# DipSeq_panel_12HP_20150408.net
KiCad netlist of a schematic drawn in EAGLE
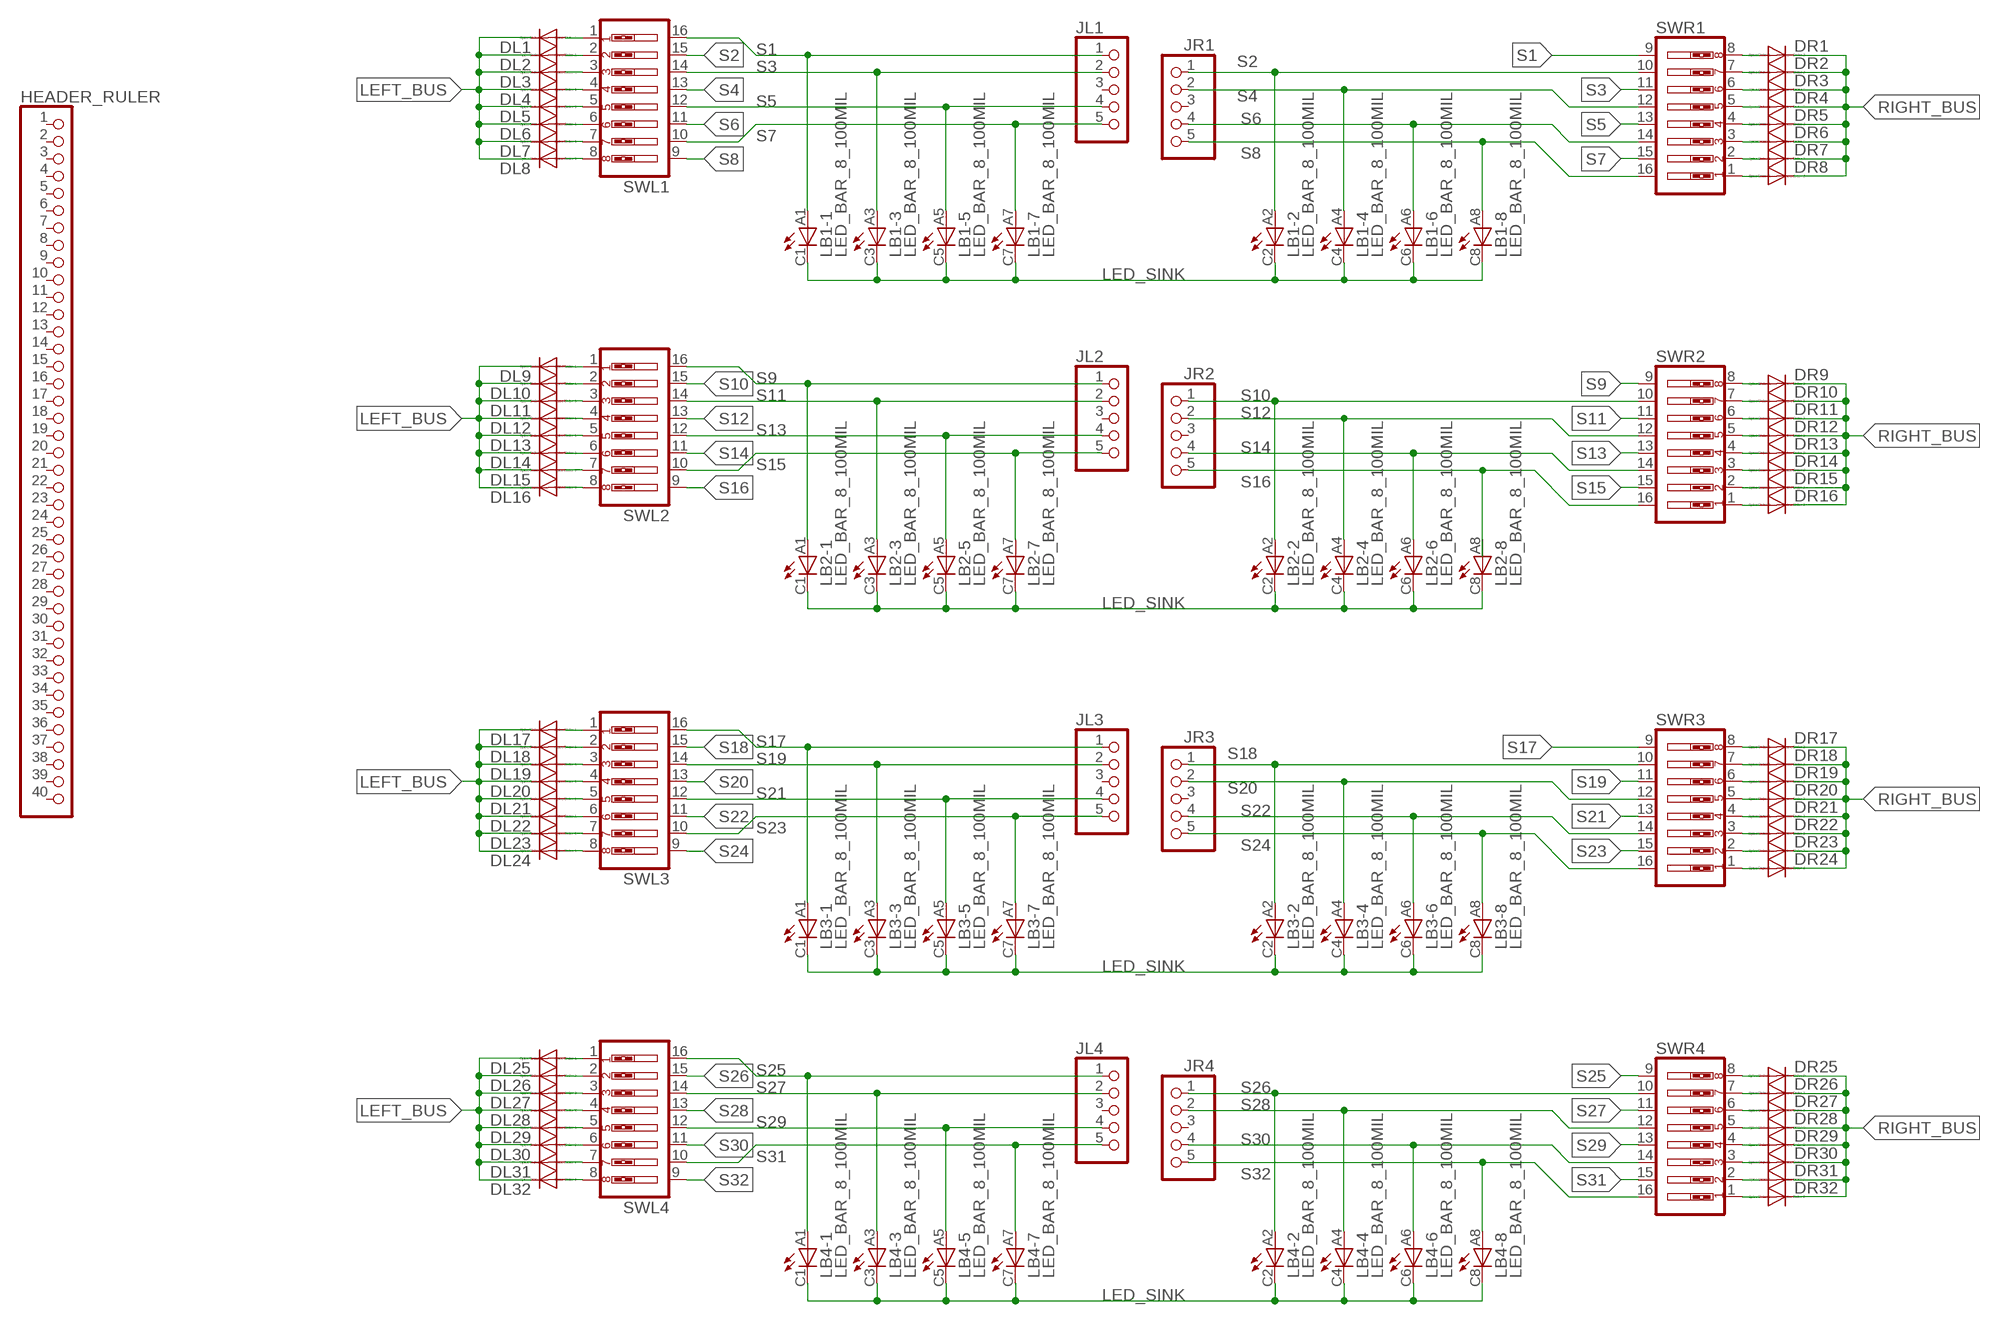
[diagram p0: schematic, sheet 1]

(export (version "E")
  (design (tool "Eeschema 10.0.6"))
  (components
    (comp (ref "DL1")
      (value "DIODE-SOD323-W")
      (footprint "eagle-import:SOD323-W")
      (libsource (lib "eagle-import") (part "DIODE-SOD323-W"))
    )
    (comp (ref "DL2")
      (value "DIODE-SOD323-W")
      (footprint "eagle-import:SOD323-W")
      (libsource (lib "eagle-import") (part "DIODE-SOD323-W"))
    )
    (comp (ref "DL3")
      (value "DIODE-SOD323-W")
      (footprint "eagle-import:SOD323-W")
      (libsource (lib "eagle-import") (part "DIODE-SOD323-W"))
    )
    (comp (ref "DL4")
      (value "DIODE-SOD323-W")
      (footprint "eagle-import:SOD323-W")
      (libsource (lib "eagle-import") (part "DIODE-SOD323-W"))
    )
    (comp (ref "DL5")
      (value "DIODE-SOD323-W")
      (footprint "eagle-import:SOD323-W")
      (libsource (lib "eagle-import") (part "DIODE-SOD323-W"))
    )
    (comp (ref "DL6")
      (value "DIODE-SOD323-W")
      (footprint "eagle-import:SOD323-W")
      (libsource (lib "eagle-import") (part "DIODE-SOD323-W"))
    )
    (comp (ref "DL7")
      (value "DIODE-SOD323-W")
      (footprint "eagle-import:SOD323-W")
      (libsource (lib "eagle-import") (part "DIODE-SOD323-W"))
    )
    (comp (ref "DL8")
      (value "DIODE-SOD323-W")
      (footprint "eagle-import:SOD323-W")
      (libsource (lib "eagle-import") (part "DIODE-SOD323-W"))
    )
    (comp (ref "DL9")
      (value "DIODE-SOD323-W")
      (footprint "eagle-import:SOD323-W")
      (libsource (lib "eagle-import") (part "DIODE-SOD323-W"))
    )
    (comp (ref "DL10")
      (value "DIODE-SOD323-W")
      (footprint "eagle-import:SOD323-W")
      (libsource (lib "eagle-import") (part "DIODE-SOD323-W"))
    )
    (comp (ref "DL11")
      (value "DIODE-SOD323-W")
      (footprint "eagle-import:SOD323-W")
      (libsource (lib "eagle-import") (part "DIODE-SOD323-W"))
    )
    (comp (ref "DL12")
      (value "DIODE-SOD323-W")
      (footprint "eagle-import:SOD323-W")
      (libsource (lib "eagle-import") (part "DIODE-SOD323-W"))
    )
    (comp (ref "DL13")
      (value "DIODE-SOD323-W")
      (footprint "eagle-import:SOD323-W")
      (libsource (lib "eagle-import") (part "DIODE-SOD323-W"))
    )
    (comp (ref "DL14")
      (value "DIODE-SOD323-W")
      (footprint "eagle-import:SOD323-W")
      (libsource (lib "eagle-import") (part "DIODE-SOD323-W"))
    )
    (comp (ref "DL15")
      (value "DIODE-SOD323-W")
      (footprint "eagle-import:SOD323-W")
      (libsource (lib "eagle-import") (part "DIODE-SOD323-W"))
    )
    (comp (ref "DL16")
      (value "DIODE-SOD323-W")
      (footprint "eagle-import:SOD323-W")
      (libsource (lib "eagle-import") (part "DIODE-SOD323-W"))
    )
    (comp (ref "DL17")
      (value "DIODE-SOD323-W")
      (footprint "eagle-import:SOD323-W")
      (libsource (lib "eagle-import") (part "DIODE-SOD323-W"))
    )
    (comp (ref "DL18")
      (value "DIODE-SOD323-W")
      (footprint "eagle-import:SOD323-W")
      (libsource (lib "eagle-import") (part "DIODE-SOD323-W"))
    )
    (comp (ref "DL19")
      (value "DIODE-SOD323-W")
      (footprint "eagle-import:SOD323-W")
      (libsource (lib "eagle-import") (part "DIODE-SOD323-W"))
    )
    (comp (ref "DL20")
      (value "DIODE-SOD323-W")
      (footprint "eagle-import:SOD323-W")
      (libsource (lib "eagle-import") (part "DIODE-SOD323-W"))
    )
    (comp (ref "DL21")
      (value "DIODE-SOD323-W")
      (footprint "eagle-import:SOD323-W")
      (libsource (lib "eagle-import") (part "DIODE-SOD323-W"))
    )
    (comp (ref "DL22")
      (value "DIODE-SOD323-W")
      (footprint "eagle-import:SOD323-W")
      (libsource (lib "eagle-import") (part "DIODE-SOD323-W"))
    )
    (comp (ref "DL23")
      (value "DIODE-SOD323-W")
      (footprint "eagle-import:SOD323-W")
      (libsource (lib "eagle-import") (part "DIODE-SOD323-W"))
    )
    (comp (ref "DL24")
      (value "DIODE-SOD323-W")
      (footprint "eagle-import:SOD323-W")
      (libsource (lib "eagle-import") (part "DIODE-SOD323-W"))
    )
    (comp (ref "DL25")
      (value "DIODE-SOD323-W")
      (footprint "eagle-import:SOD323-W")
      (libsource (lib "eagle-import") (part "DIODE-SOD323-W"))
    )
    (comp (ref "DL26")
      (value "DIODE-SOD323-W")
      (footprint "eagle-import:SOD323-W")
      (libsource (lib "eagle-import") (part "DIODE-SOD323-W"))
    )
    (comp (ref "DL27")
      (value "DIODE-SOD323-W")
      (footprint "eagle-import:SOD323-W")
      (libsource (lib "eagle-import") (part "DIODE-SOD323-W"))
    )
    (comp (ref "DL28")
      (value "DIODE-SOD323-W")
      (footprint "eagle-import:SOD323-W")
      (libsource (lib "eagle-import") (part "DIODE-SOD323-W"))
    )
    (comp (ref "DL29")
      (value "DIODE-SOD323-W")
      (footprint "eagle-import:SOD323-W")
      (libsource (lib "eagle-import") (part "DIODE-SOD323-W"))
    )
    (comp (ref "DL30")
      (value "DIODE-SOD323-W")
      (footprint "eagle-import:SOD323-W")
      (libsource (lib "eagle-import") (part "DIODE-SOD323-W"))
    )
    (comp (ref "DL31")
      (value "DIODE-SOD323-W")
      (footprint "eagle-import:SOD323-W")
      (libsource (lib "eagle-import") (part "DIODE-SOD323-W"))
    )
    (comp (ref "DL32")
      (value "DIODE-SOD323-W")
      (footprint "eagle-import:SOD323-W")
      (libsource (lib "eagle-import") (part "DIODE-SOD323-W"))
    )
    (comp (ref "DR1")
      (value "DIODE-SOD323-W")
      (footprint "eagle-import:SOD323-W")
      (libsource (lib "eagle-import") (part "DIODE-SOD323-W"))
    )
    (comp (ref "DR2")
      (value "DIODE-SOD323-W")
      (footprint "eagle-import:SOD323-W")
      (libsource (lib "eagle-import") (part "DIODE-SOD323-W"))
    )
    (comp (ref "DR3")
      (value "DIODE-SOD323-W")
      (footprint "eagle-import:SOD323-W")
      (libsource (lib "eagle-import") (part "DIODE-SOD323-W"))
    )
    (comp (ref "DR4")
      (value "DIODE-SOD323-W")
      (footprint "eagle-import:SOD323-W")
      (libsource (lib "eagle-import") (part "DIODE-SOD323-W"))
    )
    (comp (ref "DR5")
      (value "DIODE-SOD323-W")
      (footprint "eagle-import:SOD323-W")
      (libsource (lib "eagle-import") (part "DIODE-SOD323-W"))
    )
    (comp (ref "DR6")
      (value "DIODE-SOD323-W")
      (footprint "eagle-import:SOD323-W")
      (libsource (lib "eagle-import") (part "DIODE-SOD323-W"))
    )
    (comp (ref "DR7")
      (value "DIODE-SOD323-W")
      (footprint "eagle-import:SOD323-W")
      (libsource (lib "eagle-import") (part "DIODE-SOD323-W"))
    )
    (comp (ref "DR8")
      (value "DIODE-SOD323-W")
      (footprint "eagle-import:SOD323-W")
      (libsource (lib "eagle-import") (part "DIODE-SOD323-W"))
    )
    (comp (ref "DR9")
      (value "DIODE-SOD323-W")
      (footprint "eagle-import:SOD323-W")
      (libsource (lib "eagle-import") (part "DIODE-SOD323-W"))
    )
    (comp (ref "DR10")
      (value "DIODE-SOD323-W")
      (footprint "eagle-import:SOD323-W")
      (libsource (lib "eagle-import") (part "DIODE-SOD323-W"))
    )
    (comp (ref "DR11")
      (value "DIODE-SOD323-W")
      (footprint "eagle-import:SOD323-W")
      (libsource (lib "eagle-import") (part "DIODE-SOD323-W"))
    )
    (comp (ref "DR12")
      (value "DIODE-SOD323-W")
      (footprint "eagle-import:SOD323-W")
      (libsource (lib "eagle-import") (part "DIODE-SOD323-W"))
    )
    (comp (ref "DR13")
      (value "DIODE-SOD323-W")
      (footprint "eagle-import:SOD323-W")
      (libsource (lib "eagle-import") (part "DIODE-SOD323-W"))
    )
    (comp (ref "DR14")
      (value "DIODE-SOD323-W")
      (footprint "eagle-import:SOD323-W")
      (libsource (lib "eagle-import") (part "DIODE-SOD323-W"))
    )
    (comp (ref "DR15")
      (value "DIODE-SOD323-W")
      (footprint "eagle-import:SOD323-W")
      (libsource (lib "eagle-import") (part "DIODE-SOD323-W"))
    )
    (comp (ref "DR16")
      (value "DIODE-SOD323-W")
      (footprint "eagle-import:SOD323-W")
      (libsource (lib "eagle-import") (part "DIODE-SOD323-W"))
    )
    (comp (ref "DR17")
      (value "DIODE-SOD323-W")
      (footprint "eagle-import:SOD323-W")
      (libsource (lib "eagle-import") (part "DIODE-SOD323-W"))
    )
    (comp (ref "DR18")
      (value "DIODE-SOD323-W")
      (footprint "eagle-import:SOD323-W")
      (libsource (lib "eagle-import") (part "DIODE-SOD323-W"))
    )
    (comp (ref "DR19")
      (value "DIODE-SOD323-W")
      (footprint "eagle-import:SOD323-W")
      (libsource (lib "eagle-import") (part "DIODE-SOD323-W"))
    )
    (comp (ref "DR20")
      (value "DIODE-SOD323-W")
      (footprint "eagle-import:SOD323-W")
      (libsource (lib "eagle-import") (part "DIODE-SOD323-W"))
    )
    (comp (ref "DR21")
      (value "DIODE-SOD323-W")
      (footprint "eagle-import:SOD323-W")
      (libsource (lib "eagle-import") (part "DIODE-SOD323-W"))
    )
    (comp (ref "DR22")
      (value "DIODE-SOD323-W")
      (footprint "eagle-import:SOD323-W")
      (libsource (lib "eagle-import") (part "DIODE-SOD323-W"))
    )
    (comp (ref "DR23")
      (value "DIODE-SOD323-W")
      (footprint "eagle-import:SOD323-W")
      (libsource (lib "eagle-import") (part "DIODE-SOD323-W"))
    )
    (comp (ref "DR24")
      (value "DIODE-SOD323-W")
      (footprint "eagle-import:SOD323-W")
      (libsource (lib "eagle-import") (part "DIODE-SOD323-W"))
    )
    (comp (ref "DR25")
      (value "DIODE-SOD323-W")
      (footprint "eagle-import:SOD323-W")
      (libsource (lib "eagle-import") (part "DIODE-SOD323-W"))
    )
    (comp (ref "DR26")
      (value "DIODE-SOD323-W")
      (footprint "eagle-import:SOD323-W")
      (libsource (lib "eagle-import") (part "DIODE-SOD323-W"))
    )
    (comp (ref "DR27")
      (value "DIODE-SOD323-W")
      (footprint "eagle-import:SOD323-W")
      (libsource (lib "eagle-import") (part "DIODE-SOD323-W"))
    )
    (comp (ref "DR28")
      (value "DIODE-SOD323-W")
      (footprint "eagle-import:SOD323-W")
      (libsource (lib "eagle-import") (part "DIODE-SOD323-W"))
    )
    (comp (ref "DR29")
      (value "DIODE-SOD323-W")
      (footprint "eagle-import:SOD323-W")
      (libsource (lib "eagle-import") (part "DIODE-SOD323-W"))
    )
    (comp (ref "DR30")
      (value "DIODE-SOD323-W")
      (footprint "eagle-import:SOD323-W")
      (libsource (lib "eagle-import") (part "DIODE-SOD323-W"))
    )
    (comp (ref "DR31")
      (value "DIODE-SOD323-W")
      (footprint "eagle-import:SOD323-W")
      (libsource (lib "eagle-import") (part "DIODE-SOD323-W"))
    )
    (comp (ref "DR32")
      (value "DIODE-SOD323-W")
      (footprint "eagle-import:SOD323-W")
      (libsource (lib "eagle-import") (part "DIODE-SOD323-W"))
    )
    (comp (ref "HEADER_RULER")
      (value "PINHD-1X40")
      (footprint "eagle-import:1X40")
      (libsource (lib "eagle-import") (part "PINHD-1X40"))
    )
    (comp (ref "JL1")
      (value "PINHD-1X5")
      (footprint "eagle-import:1X05")
      (libsource (lib "eagle-import") (part "PINHD-1X5"))
    )
    (comp (ref "JL2")
      (value "PINHD-1X5")
      (footprint "eagle-import:1X05")
      (libsource (lib "eagle-import") (part "PINHD-1X5"))
    )
    (comp (ref "JL3")
      (value "PINHD-1X5")
      (footprint "eagle-import:1X05")
      (libsource (lib "eagle-import") (part "PINHD-1X5"))
    )
    (comp (ref "JL4")
      (value "PINHD-1X5")
      (footprint "eagle-import:1X05")
      (libsource (lib "eagle-import") (part "PINHD-1X5"))
    )
    (comp (ref "JR1")
      (value "PINHD-1X5")
      (footprint "eagle-import:1X05")
      (libsource (lib "eagle-import") (part "PINHD-1X5"))
    )
    (comp (ref "JR2")
      (value "PINHD-1X5")
      (footprint "eagle-import:1X05")
      (libsource (lib "eagle-import") (part "PINHD-1X5"))
    )
    (comp (ref "JR3")
      (value "PINHD-1X5")
      (footprint "eagle-import:1X05")
      (libsource (lib "eagle-import") (part "PINHD-1X5"))
    )
    (comp (ref "JR4")
      (value "PINHD-1X5")
      (footprint "eagle-import:1X05")
      (libsource (lib "eagle-import") (part "PINHD-1X5"))
    )
    (comp (ref "LB1")
      (value "LED_BAR_8_100MIL")
      (footprint "eagle-import:LED_BAR_8")
      (libsource (lib "eagle-import") (part "LED_BAR_8_100MIL"))
    )
    (comp (ref "LB2")
      (value "LED_BAR_8_100MIL")
      (footprint "eagle-import:LED_BAR_8")
      (libsource (lib "eagle-import") (part "LED_BAR_8_100MIL"))
    )
    (comp (ref "LB3")
      (value "LED_BAR_8_100MIL")
      (footprint "eagle-import:LED_BAR_8")
      (libsource (lib "eagle-import") (part "LED_BAR_8_100MIL"))
    )
    (comp (ref "LB4")
      (value "LED_BAR_8_100MIL")
      (footprint "eagle-import:LED_BAR_8")
      (libsource (lib "eagle-import") (part "LED_BAR_8_100MIL"))
    )
    (comp (ref "SWL1")
      (value "SW_DIP-8PIANO_STYLE")
      (footprint "eagle-import:PIANO_DIPSWITCH_08")
      (libsource (lib "eagle-import") (part "SW_DIP-8PIANO_STYLE"))
    )
    (comp (ref "SWL2")
      (value "SW_DIP-8PIANO_STYLE")
      (footprint "eagle-import:PIANO_DIPSWITCH_08")
      (libsource (lib "eagle-import") (part "SW_DIP-8PIANO_STYLE"))
    )
    (comp (ref "SWL3")
      (value "SW_DIP-8PIANO_STYLE")
      (footprint "eagle-import:PIANO_DIPSWITCH_08")
      (libsource (lib "eagle-import") (part "SW_DIP-8PIANO_STYLE"))
    )
    (comp (ref "SWL4")
      (value "SW_DIP-8PIANO_STYLE")
      (footprint "eagle-import:PIANO_DIPSWITCH_08")
      (libsource (lib "eagle-import") (part "SW_DIP-8PIANO_STYLE"))
    )
    (comp (ref "SWR1")
      (value "SW_DIP-8PIANO_STYLE")
      (footprint "eagle-import:PIANO_DIPSWITCH_08")
      (libsource (lib "eagle-import") (part "SW_DIP-8PIANO_STYLE"))
    )
    (comp (ref "SWR2")
      (value "SW_DIP-8PIANO_STYLE")
      (footprint "eagle-import:PIANO_DIPSWITCH_08")
      (libsource (lib "eagle-import") (part "SW_DIP-8PIANO_STYLE"))
    )
    (comp (ref "SWR3")
      (value "SW_DIP-8PIANO_STYLE")
      (footprint "eagle-import:PIANO_DIPSWITCH_08")
      (libsource (lib "eagle-import") (part "SW_DIP-8PIANO_STYLE"))
    )
    (comp (ref "SWR4")
      (value "SW_DIP-8PIANO_STYLE")
      (footprint "eagle-import:PIANO_DIPSWITCH_08")
      (libsource (lib "eagle-import") (part "SW_DIP-8PIANO_STYLE"))
    )
  )
  (nets
    (net (code "1") (name "/LED_SINK") (class "Default")
      (node (ref "LB1") (pin "C1") (pinfunction "C_C1") (pintype "passive"))
      (node (ref "LB1") (pin "C2") (pinfunction "C_C2") (pintype "passive"))
      (node (ref "LB1") (pin "C3") (pinfunction "C_C3") (pintype "passive"))
      (node (ref "LB1") (pin "C4") (pinfunction "C_C4") (pintype "passive"))
      (node (ref "LB1") (pin "C5") (pinfunction "C_C5") (pintype "passive"))
      (node (ref "LB1") (pin "C6") (pinfunction "C_C6") (pintype "passive"))
      (node (ref "LB1") (pin "C7") (pinfunction "C_C7") (pintype "passive"))
      (node (ref "LB1") (pin "C8") (pinfunction "C_C8") (pintype "passive"))
      (node (ref "LB2") (pin "C1") (pinfunction "C_C1") (pintype "passive"))
      (node (ref "LB2") (pin "C2") (pinfunction "C_C2") (pintype "passive"))
      (node (ref "LB2") (pin "C3") (pinfunction "C_C3") (pintype "passive"))
      (node (ref "LB2") (pin "C4") (pinfunction "C_C4") (pintype "passive"))
      (node (ref "LB2") (pin "C5") (pinfunction "C_C5") (pintype "passive"))
      (node (ref "LB2") (pin "C6") (pinfunction "C_C6") (pintype "passive"))
      (node (ref "LB2") (pin "C7") (pinfunction "C_C7") (pintype "passive"))
      (node (ref "LB2") (pin "C8") (pinfunction "C_C8") (pintype "passive"))
      (node (ref "LB3") (pin "C1") (pinfunction "C_C1") (pintype "passive"))
      (node (ref "LB3") (pin "C2") (pinfunction "C_C2") (pintype "passive"))
      (node (ref "LB3") (pin "C3") (pinfunction "C_C3") (pintype "passive"))
      (node (ref "LB3") (pin "C4") (pinfunction "C_C4") (pintype "passive"))
      (node (ref "LB3") (pin "C5") (pinfunction "C_C5") (pintype "passive"))
      (node (ref "LB3") (pin "C6") (pinfunction "C_C6") (pintype "passive"))
      (node (ref "LB3") (pin "C7") (pinfunction "C_C7") (pintype "passive"))
      (node (ref "LB3") (pin "C8") (pinfunction "C_C8") (pintype "passive"))
      (node (ref "LB4") (pin "C1") (pinfunction "C_C1") (pintype "passive"))
      (node (ref "LB4") (pin "C2") (pinfunction "C_C2") (pintype "passive"))
      (node (ref "LB4") (pin "C3") (pinfunction "C_C3") (pintype "passive"))
      (node (ref "LB4") (pin "C4") (pinfunction "C_C4") (pintype "passive"))
      (node (ref "LB4") (pin "C5") (pinfunction "C_C5") (pintype "passive"))
      (node (ref "LB4") (pin "C6") (pinfunction "C_C6") (pintype "passive"))
      (node (ref "LB4") (pin "C7") (pinfunction "C_C7") (pintype "passive"))
      (node (ref "LB4") (pin "C8") (pinfunction "C_C8") (pintype "passive"))
    )
    (net (code "2") (name "LEFT_BUS") (class "Default")
      (node (ref "DL1") (pin "C") (pinfunction "C_C") (pintype "passive"))
      (node (ref "DL10") (pin "C") (pinfunction "C_C") (pintype "passive"))
      (node (ref "DL11") (pin "C") (pinfunction "C_C") (pintype "passive"))
      (node (ref "DL12") (pin "C") (pinfunction "C_C") (pintype "passive"))
      (node (ref "DL13") (pin "C") (pinfunction "C_C") (pintype "passive"))
      (node (ref "DL14") (pin "C") (pinfunction "C_C") (pintype "passive"))
      (node (ref "DL15") (pin "C") (pinfunction "C_C") (pintype "passive"))
      (node (ref "DL16") (pin "C") (pinfunction "C_C") (pintype "passive"))
      (node (ref "DL17") (pin "C") (pinfunction "C_C") (pintype "passive"))
      (node (ref "DL18") (pin "C") (pinfunction "C_C") (pintype "passive"))
      (node (ref "DL19") (pin "C") (pinfunction "C_C") (pintype "passive"))
      (node (ref "DL2") (pin "C") (pinfunction "C_C") (pintype "passive"))
      (node (ref "DL20") (pin "C") (pinfunction "C_C") (pintype "passive"))
      (node (ref "DL21") (pin "C") (pinfunction "C_C") (pintype "passive"))
      (node (ref "DL22") (pin "C") (pinfunction "C_C") (pintype "passive"))
      (node (ref "DL23") (pin "C") (pinfunction "C_C") (pintype "passive"))
      (node (ref "DL24") (pin "C") (pinfunction "C_C") (pintype "passive"))
      (node (ref "DL25") (pin "C") (pinfunction "C_C") (pintype "passive"))
      (node (ref "DL26") (pin "C") (pinfunction "C_C") (pintype "passive"))
      (node (ref "DL27") (pin "C") (pinfunction "C_C") (pintype "passive"))
      (node (ref "DL28") (pin "C") (pinfunction "C_C") (pintype "passive"))
      (node (ref "DL29") (pin "C") (pinfunction "C_C") (pintype "passive"))
      (node (ref "DL3") (pin "C") (pinfunction "C_C") (pintype "passive"))
      (node (ref "DL30") (pin "C") (pinfunction "C_C") (pintype "passive"))
      (node (ref "DL31") (pin "C") (pinfunction "C_C") (pintype "passive"))
      (node (ref "DL32") (pin "C") (pinfunction "C_C") (pintype "passive"))
      (node (ref "DL4") (pin "C") (pinfunction "C_C") (pintype "passive"))
      (node (ref "DL5") (pin "C") (pinfunction "C_C") (pintype "passive"))
      (node (ref "DL6") (pin "C") (pinfunction "C_C") (pintype "passive"))
      (node (ref "DL7") (pin "C") (pinfunction "C_C") (pintype "passive"))
      (node (ref "DL8") (pin "C") (pinfunction "C_C") (pintype "passive"))
      (node (ref "DL9") (pin "C") (pinfunction "C_C") (pintype "passive"))
    )
    (net (code "3") (name "Net-(DL1-PadA)") (class "Default")
      (node (ref "DL1") (pin "A") (pinfunction "A_A") (pintype "passive"))
      (node (ref "SWL1") (pin "1") (pinfunction "1_1") (pintype "passive"))
    )
    (net (code "4") (name "Net-(DL2-PadA)") (class "Default")
      (node (ref "DL2") (pin "A") (pinfunction "A_A") (pintype "passive"))
      (node (ref "SWL1") (pin "2") (pinfunction "2_2") (pintype "passive"))
    )
    (net (code "5") (name "Net-(DL3-PadA)") (class "Default")
      (node (ref "DL3") (pin "A") (pinfunction "A_A") (pintype "passive"))
      (node (ref "SWL1") (pin "3") (pinfunction "3_3") (pintype "passive"))
    )
    (net (code "6") (name "Net-(DL4-PadA)") (class "Default")
      (node (ref "DL4") (pin "A") (pinfunction "A_A") (pintype "passive"))
      (node (ref "SWL1") (pin "4") (pinfunction "4_4") (pintype "passive"))
    )
    (net (code "7") (name "Net-(DL5-PadA)") (class "Default")
      (node (ref "DL5") (pin "A") (pinfunction "A_A") (pintype "passive"))
      (node (ref "SWL1") (pin "5") (pinfunction "5_5") (pintype "passive"))
    )
    (net (code "8") (name "Net-(DL6-PadA)") (class "Default")
      (node (ref "DL6") (pin "A") (pinfunction "A_A") (pintype "passive"))
      (node (ref "SWL1") (pin "6") (pinfunction "6_6") (pintype "passive"))
    )
    (net (code "9") (name "Net-(DL7-PadA)") (class "Default")
      (node (ref "DL7") (pin "A") (pinfunction "A_A") (pintype "passive"))
      (node (ref "SWL1") (pin "7") (pinfunction "7_7") (pintype "passive"))
    )
    (net (code "10") (name "Net-(DL8-PadA)") (class "Default")
      (node (ref "DL8") (pin "A") (pinfunction "A_A") (pintype "passive"))
      (node (ref "SWL1") (pin "8") (pinfunction "8_8") (pintype "passive"))
    )
    (net (code "11") (name "Net-(DL9-PadA)") (class "Default")
      (node (ref "DL9") (pin "A") (pinfunction "A_A") (pintype "passive"))
      (node (ref "SWL2") (pin "1") (pinfunction "1_1") (pintype "passive"))
    )
    (net (code "12") (name "Net-(DL10-PadA)") (class "Default")
      (node (ref "DL10") (pin "A") (pinfunction "A_A") (pintype "passive"))
      (node (ref "SWL2") (pin "2") (pinfunction "2_2") (pintype "passive"))
    )
    (net (code "13") (name "Net-(DL11-PadA)") (class "Default")
      (node (ref "DL11") (pin "A") (pinfunction "A_A") (pintype "passive"))
      (node (ref "SWL2") (pin "3") (pinfunction "3_3") (pintype "passive"))
    )
    (net (code "14") (name "Net-(DL12-PadA)") (class "Default")
      (node (ref "DL12") (pin "A") (pinfunction "A_A") (pintype "passive"))
      (node (ref "SWL2") (pin "4") (pinfunction "4_4") (pintype "passive"))
    )
    (net (code "15") (name "Net-(DL13-PadA)") (class "Default")
      (node (ref "DL13") (pin "A") (pinfunction "A_A") (pintype "passive"))
      (node (ref "SWL2") (pin "5") (pinfunction "5_5") (pintype "passive"))
    )
    (net (code "16") (name "Net-(DL14-PadA)") (class "Default")
      (node (ref "DL14") (pin "A") (pinfunction "A_A") (pintype "passive"))
      (node (ref "SWL2") (pin "6") (pinfunction "6_6") (pintype "passive"))
    )
    (net (code "17") (name "Net-(DL15-PadA)") (class "Default")
      (node (ref "DL15") (pin "A") (pinfunction "A_A") (pintype "passive"))
      (node (ref "SWL2") (pin "7") (pinfunction "7_7") (pintype "passive"))
    )
    (net (code "18") (name "Net-(DL16-PadA)") (class "Default")
      (node (ref "DL16") (pin "A") (pinfunction "A_A") (pintype "passive"))
      (node (ref "SWL2") (pin "8") (pinfunction "8_8") (pintype "passive"))
    )
    (net (code "19") (name "Net-(DL17-PadA)") (class "Default")
      (node (ref "DL17") (pin "A") (pinfunction "A_A") (pintype "passive"))
      (node (ref "SWL3") (pin "1") (pinfunction "1_1") (pintype "passive"))
    )
    (net (code "20") (name "Net-(DL18-PadA)") (class "Default")
      (node (ref "DL18") (pin "A") (pinfunction "A_A") (pintype "passive"))
      (node (ref "SWL3") (pin "2") (pinfunction "2_2") (pintype "passive"))
    )
    (net (code "21") (name "Net-(DL19-PadA)") (class "Default")
      (node (ref "DL19") (pin "A") (pinfunction "A_A") (pintype "passive"))
      (node (ref "SWL3") (pin "3") (pinfunction "3_3") (pintype "passive"))
    )
    (net (code "22") (name "Net-(DL20-PadA)") (class "Default")
      (node (ref "DL20") (pin "A") (pinfunction "A_A") (pintype "passive"))
      (node (ref "SWL3") (pin "4") (pinfunction "4_4") (pintype "passive"))
    )
    (net (code "23") (name "Net-(DL21-PadA)") (class "Default")
      (node (ref "DL21") (pin "A") (pinfunction "A_A") (pintype "passive"))
      (node (ref "SWL3") (pin "5") (pinfunction "5_5") (pintype "passive"))
    )
    (net (code "24") (name "Net-(DL22-PadA)") (class "Default")
      (node (ref "DL22") (pin "A") (pinfunction "A_A") (pintype "passive"))
      (node (ref "SWL3") (pin "6") (pinfunction "6_6") (pintype "passive"))
    )
    (net (code "25") (name "Net-(DL23-PadA)") (class "Default")
      (node (ref "DL23") (pin "A") (pinfunction "A_A") (pintype "passive"))
      (node (ref "SWL3") (pin "7") (pinfunction "7_7") (pintype "passive"))
    )
    (net (code "26") (name "Net-(DL24-PadA)") (class "Default")
      (node (ref "DL24") (pin "A") (pinfunction "A_A") (pintype "passive"))
      (node (ref "SWL3") (pin "8") (pinfunction "8_8") (pintype "passive"))
    )
    (net (code "27") (name "Net-(DL25-PadA)") (class "Default")
      (node (ref "DL25") (pin "A") (pinfunction "A_A") (pintype "passive"))
      (node (ref "SWL4") (pin "1") (pinfunction "1_1") (pintype "passive"))
    )
    (net (code "28") (name "Net-(DL26-PadA)") (class "Default")
      (node (ref "DL26") (pin "A") (pinfunction "A_A") (pintype "passive"))
      (node (ref "SWL4") (pin "2") (pinfunction "2_2") (pintype "passive"))
    )
    (net (code "29") (name "Net-(DL27-PadA)") (class "Default")
      (node (ref "DL27") (pin "A") (pinfunction "A_A") (pintype "passive"))
      (node (ref "SWL4") (pin "3") (pinfunction "3_3") (pintype "passive"))
    )
    (net (code "30") (name "Net-(DL28-PadA)") (class "Default")
      (node (ref "DL28") (pin "A") (pinfunction "A_A") (pintype "passive"))
      (node (ref "SWL4") (pin "4") (pinfunction "4_4") (pintype "passive"))
    )
    (net (code "31") (name "Net-(DL29-PadA)") (class "Default")
      (node (ref "DL29") (pin "A") (pinfunction "A_A") (pintype "passive"))
      (node (ref "SWL4") (pin "5") (pinfunction "5_5") (pintype "passive"))
    )
    (net (code "32") (name "Net-(DL30-PadA)") (class "Default")
      (node (ref "DL30") (pin "A") (pinfunction "A_A") (pintype "passive"))
      (node (ref "SWL4") (pin "6") (pinfunction "6_6") (pintype "passive"))
    )
    (net (code "33") (name "Net-(DL31-PadA)") (class "Default")
      (node (ref "DL31") (pin "A") (pinfunction "A_A") (pintype "passive"))
      (node (ref "SWL4") (pin "7") (pinfunction "7_7") (pintype "passive"))
    )
    (net (code "34") (name "Net-(DL32-PadA)") (class "Default")
      (node (ref "DL32") (pin "A") (pinfunction "A_A") (pintype "passive"))
      (node (ref "SWL4") (pin "8") (pinfunction "8_8") (pintype "passive"))
    )
    (net (code "35") (name "Net-(DR1-PadA)") (class "Default")
      (node (ref "DR1") (pin "A") (pinfunction "A_A") (pintype "passive"))
      (node (ref "SWR1") (pin "8") (pinfunction "8_8") (pintype "passive"))
    )
    (net (code "36") (name "Net-(DR2-PadA)") (class "Default")
      (node (ref "DR2") (pin "A") (pinfunction "A_A") (pintype "passive"))
      (node (ref "SWR1") (pin "7") (pinfunction "7_7") (pintype "passive"))
    )
    (net (code "37") (name "Net-(DR3-PadA)") (class "Default")
      (node (ref "DR3") (pin "A") (pinfunction "A_A") (pintype "passive"))
      (node (ref "SWR1") (pin "6") (pinfunction "6_6") (pintype "passive"))
    )
    (net (code "38") (name "Net-(DR4-PadA)") (class "Default")
      (node (ref "DR4") (pin "A") (pinfunction "A_A") (pintype "passive"))
      (node (ref "SWR1") (pin "5") (pinfunction "5_5") (pintype "passive"))
    )
    (net (code "39") (name "Net-(DR5-PadA)") (class "Default")
      (node (ref "DR5") (pin "A") (pinfunction "A_A") (pintype "passive"))
      (node (ref "SWR1") (pin "4") (pinfunction "4_4") (pintype "passive"))
    )
    (net (code "40") (name "Net-(DR6-PadA)") (class "Default")
      (node (ref "DR6") (pin "A") (pinfunction "A_A") (pintype "passive"))
      (node (ref "SWR1") (pin "3") (pinfunction "3_3") (pintype "passive"))
    )
    (net (code "41") (name "Net-(DR7-PadA)") (class "Default")
      (node (ref "DR7") (pin "A") (pinfunction "A_A") (pintype "passive"))
      (node (ref "SWR1") (pin "2") (pinfunction "2_2") (pintype "passive"))
    )
    (net (code "42") (name "Net-(DR8-PadA)") (class "Default")
      (node (ref "DR8") (pin "A") (pinfunction "A_A") (pintype "passive"))
      (node (ref "SWR1") (pin "1") (pinfunction "1_1") (pintype "passive"))
    )
    (net (code "43") (name "Net-(DR9-PadA)") (class "Default")
      (node (ref "DR9") (pin "A") (pinfunction "A_A") (pintype "passive"))
      (node (ref "SWR2") (pin "8") (pinfunction "8_8") (pintype "passive"))
    )
    (net (code "44") (name "Net-(DR10-PadA)") (class "Default")
      (node (ref "DR10") (pin "A") (pinfunction "A_A") (pintype "passive"))
      (node (ref "SWR2") (pin "7") (pinfunction "7_7") (pintype "passive"))
    )
    (net (code "45") (name "Net-(DR11-PadA)") (class "Default")
      (node (ref "DR11") (pin "A") (pinfunction "A_A") (pintype "passive"))
      (node (ref "SWR2") (pin "6") (pinfunction "6_6") (pintype "passive"))
    )
    (net (code "46") (name "Net-(DR12-PadA)") (class "Default")
      (node (ref "DR12") (pin "A") (pinfunction "A_A") (pintype "passive"))
      (node (ref "SWR2") (pin "5") (pinfunction "5_5") (pintype "passive"))
    )
    (net (code "47") (name "Net-(DR13-PadA)") (class "Default")
      (node (ref "DR13") (pin "A") (pinfunction "A_A") (pintype "passive"))
      (node (ref "SWR2") (pin "4") (pinfunction "4_4") (pintype "passive"))
    )
    (net (code "48") (name "Net-(DR14-PadA)") (class "Default")
      (node (ref "DR14") (pin "A") (pinfunction "A_A") (pintype "passive"))
      (node (ref "SWR2") (pin "3") (pinfunction "3_3") (pintype "passive"))
    )
    (net (code "49") (name "Net-(DR15-PadA)") (class "Default")
      (node (ref "DR15") (pin "A") (pinfunction "A_A") (pintype "passive"))
      (node (ref "SWR2") (pin "2") (pinfunction "2_2") (pintype "passive"))
    )
    (net (code "50") (name "Net-(DR16-PadA)") (class "Default")
      (node (ref "DR16") (pin "A") (pinfunction "A_A") (pintype "passive"))
      (node (ref "SWR2") (pin "1") (pinfunction "1_1") (pintype "passive"))
    )
    (net (code "51") (name "Net-(DR17-PadA)") (class "Default")
      (node (ref "DR17") (pin "A") (pinfunction "A_A") (pintype "passive"))
      (node (ref "SWR3") (pin "8") (pinfunction "8_8") (pintype "passive"))
    )
    (net (code "52") (name "Net-(DR18-PadA)") (class "Default")
      (node (ref "DR18") (pin "A") (pinfunction "A_A") (pintype "passive"))
      (node (ref "SWR3") (pin "7") (pinfunction "7_7") (pintype "passive"))
    )
    (net (code "53") (name "Net-(DR19-PadA)") (class "Default")
      (node (ref "DR19") (pin "A") (pinfunction "A_A") (pintype "passive"))
      (node (ref "SWR3") (pin "6") (pinfunction "6_6") (pintype "passive"))
    )
    (net (code "54") (name "Net-(DR20-PadA)") (class "Default")
      (node (ref "DR20") (pin "A") (pinfunction "A_A") (pintype "passive"))
      (node (ref "SWR3") (pin "5") (pinfunction "5_5") (pintype "passive"))
    )
    (net (code "55") (name "Net-(DR21-PadA)") (class "Default")
      (node (ref "DR21") (pin "A") (pinfunction "A_A") (pintype "passive"))
      (node (ref "SWR3") (pin "4") (pinfunction "4_4") (pintype "passive"))
    )
    (net (code "56") (name "Net-(DR22-PadA)") (class "Default")
      (node (ref "DR22") (pin "A") (pinfunction "A_A") (pintype "passive"))
      (node (ref "SWR3") (pin "3") (pinfunction "3_3") (pintype "passive"))
    )
    (net (code "57") (name "Net-(DR23-PadA)") (class "Default")
      (node (ref "DR23") (pin "A") (pinfunction "A_A") (pintype "passive"))
      (node (ref "SWR3") (pin "2") (pinfunction "2_2") (pintype "passive"))
    )
    (net (code "58") (name "Net-(DR24-PadA)") (class "Default")
      (node (ref "DR24") (pin "A") (pinfunction "A_A") (pintype "passive"))
      (node (ref "SWR3") (pin "1") (pinfunction "1_1") (pintype "passive"))
    )
    (net (code "59") (name "Net-(DR25-PadA)") (class "Default")
      (node (ref "DR25") (pin "A") (pinfunction "A_A") (pintype "passive"))
      (node (ref "SWR4") (pin "8") (pinfunction "8_8") (pintype "passive"))
    )
    (net (code "60") (name "Net-(DR26-PadA)") (class "Default")
      (node (ref "DR26") (pin "A") (pinfunction "A_A") (pintype "passive"))
      (node (ref "SWR4") (pin "7") (pinfunction "7_7") (pintype "passive"))
    )
    (net (code "61") (name "Net-(DR27-PadA)") (class "Default")
      (node (ref "DR27") (pin "A") (pinfunction "A_A") (pintype "passive"))
      (node (ref "SWR4") (pin "6") (pinfunction "6_6") (pintype "passive"))
    )
    (net (code "62") (name "Net-(DR28-PadA)") (class "Default")
      (node (ref "DR28") (pin "A") (pinfunction "A_A") (pintype "passive"))
      (node (ref "SWR4") (pin "5") (pinfunction "5_5") (pintype "passive"))
    )
    (net (code "63") (name "Net-(DR29-PadA)") (class "Default")
      (node (ref "DR29") (pin "A") (pinfunction "A_A") (pintype "passive"))
      (node (ref "SWR4") (pin "4") (pinfunction "4_4") (pintype "passive"))
    )
    (net (code "64") (name "Net-(DR30-PadA)") (class "Default")
      (node (ref "DR30") (pin "A") (pinfunction "A_A") (pintype "passive"))
      (node (ref "SWR4") (pin "3") (pinfunction "3_3") (pintype "passive"))
    )
    (net (code "65") (name "Net-(DR31-PadA)") (class "Default")
      (node (ref "DR31") (pin "A") (pinfunction "A_A") (pintype "passive"))
      (node (ref "SWR4") (pin "2") (pinfunction "2_2") (pintype "passive"))
    )
    (net (code "66") (name "Net-(DR32-PadA)") (class "Default")
      (node (ref "DR32") (pin "A") (pinfunction "A_A") (pintype "passive"))
      (node (ref "SWR4") (pin "1") (pinfunction "1_1") (pintype "passive"))
    )
    (net (code "67") (name "RIGHT_BUS") (class "Default")
      (node (ref "DR1") (pin "C") (pinfunction "C_C") (pintype "passive"))
      (node (ref "DR10") (pin "C") (pinfunction "C_C") (pintype "passive"))
      (node (ref "DR11") (pin "C") (pinfunction "C_C") (pintype "passive"))
      (node (ref "DR12") (pin "C") (pinfunction "C_C") (pintype "passive"))
      (node (ref "DR13") (pin "C") (pinfunction "C_C") (pintype "passive"))
      (node (ref "DR14") (pin "C") (pinfunction "C_C") (pintype "passive"))
      (node (ref "DR15") (pin "C") (pinfunction "C_C") (pintype "passive"))
      (node (ref "DR16") (pin "C") (pinfunction "C_C") (pintype "passive"))
      (node (ref "DR17") (pin "C") (pinfunction "C_C") (pintype "passive"))
      (node (ref "DR18") (pin "C") (pinfunction "C_C") (pintype "passive"))
      (node (ref "DR19") (pin "C") (pinfunction "C_C") (pintype "passive"))
      (node (ref "DR2") (pin "C") (pinfunction "C_C") (pintype "passive"))
      (node (ref "DR20") (pin "C") (pinfunction "C_C") (pintype "passive"))
      (node (ref "DR21") (pin "C") (pinfunction "C_C") (pintype "passive"))
      (node (ref "DR22") (pin "C") (pinfunction "C_C") (pintype "passive"))
      (node (ref "DR23") (pin "C") (pinfunction "C_C") (pintype "passive"))
      (node (ref "DR24") (pin "C") (pinfunction "C_C") (pintype "passive"))
      (node (ref "DR25") (pin "C") (pinfunction "C_C") (pintype "passive"))
      (node (ref "DR26") (pin "C") (pinfunction "C_C") (pintype "passive"))
      (node (ref "DR27") (pin "C") (pinfunction "C_C") (pintype "passive"))
      (node (ref "DR28") (pin "C") (pinfunction "C_C") (pintype "passive"))
      (node (ref "DR29") (pin "C") (pinfunction "C_C") (pintype "passive"))
      (node (ref "DR3") (pin "C") (pinfunction "C_C") (pintype "passive"))
      (node (ref "DR30") (pin "C") (pinfunction "C_C") (pintype "passive"))
      (node (ref "DR31") (pin "C") (pinfunction "C_C") (pintype "passive"))
      (node (ref "DR32") (pin "C") (pinfunction "C_C") (pintype "passive"))
      (node (ref "DR4") (pin "C") (pinfunction "C_C") (pintype "passive"))
      (node (ref "DR5") (pin "C") (pinfunction "C_C") (pintype "passive"))
      (node (ref "DR6") (pin "C") (pinfunction "C_C") (pintype "passive"))
      (node (ref "DR7") (pin "C") (pinfunction "C_C") (pintype "passive"))
      (node (ref "DR8") (pin "C") (pinfunction "C_C") (pintype "passive"))
      (node (ref "DR9") (pin "C") (pinfunction "C_C") (pintype "passive"))
    )
    (net (code "68") (name "S1") (class "Default")
      (node (ref "JL1") (pin "1") (pinfunction "1_1") (pintype "passive"))
      (node (ref "LB1") (pin "A1") (pinfunction "A_A1") (pintype "passive"))
      (node (ref "SWL1") (pin "16") (pinfunction "16_16") (pintype "passive"))
      (node (ref "SWR1") (pin "9") (pinfunction "9_9") (pintype "passive"))
    )
    (net (code "69") (name "S2") (class "Default")
      (node (ref "JR1") (pin "1") (pinfunction "1_1") (pintype "passive"))
      (node (ref "LB1") (pin "A2") (pinfunction "A_A2") (pintype "passive"))
      (node (ref "SWL1") (pin "15") (pinfunction "15_15") (pintype "passive"))
      (node (ref "SWR1") (pin "10") (pinfunction "10_10") (pintype "passive"))
    )
    (net (code "70") (name "S3") (class "Default")
      (node (ref "JL1") (pin "2") (pinfunction "2_2") (pintype "passive"))
      (node (ref "LB1") (pin "A3") (pinfunction "A_A3") (pintype "passive"))
      (node (ref "SWL1") (pin "14") (pinfunction "14_14") (pintype "passive"))
      (node (ref "SWR1") (pin "11") (pinfunction "11_11") (pintype "passive"))
    )
    (net (code "71") (name "S4") (class "Default")
      (node (ref "JR1") (pin "2") (pinfunction "2_2") (pintype "passive"))
      (node (ref "LB1") (pin "A4") (pinfunction "A_A4") (pintype "passive"))
      (node (ref "SWL1") (pin "13") (pinfunction "13_13") (pintype "passive"))
      (node (ref "SWR1") (pin "12") (pinfunction "12_12") (pintype "passive"))
    )
    (net (code "72") (name "S5") (class "Default")
      (node (ref "JL1") (pin "4") (pinfunction "4_4") (pintype "passive"))
      (node (ref "LB1") (pin "A5") (pinfunction "A_A5") (pintype "passive"))
      (node (ref "SWL1") (pin "12") (pinfunction "12_12") (pintype "passive"))
      (node (ref "SWR1") (pin "13") (pinfunction "13_13") (pintype "passive"))
    )
    (net (code "73") (name "S6") (class "Default")
      (node (ref "JR1") (pin "4") (pinfunction "4_4") (pintype "passive"))
      (node (ref "LB1") (pin "A6") (pinfunction "A_A6") (pintype "passive"))
      (node (ref "SWL1") (pin "11") (pinfunction "11_11") (pintype "passive"))
      (node (ref "SWR1") (pin "14") (pinfunction "14_14") (pintype "passive"))
    )
    (net (code "74") (name "S7") (class "Default")
      (node (ref "JL1") (pin "5") (pinfunction "5_5") (pintype "passive"))
      (node (ref "LB1") (pin "A7") (pinfunction "A_A7") (pintype "passive"))
      (node (ref "SWL1") (pin "10") (pinfunction "10_10") (pintype "passive"))
      (node (ref "SWR1") (pin "15") (pinfunction "15_15") (pintype "passive"))
    )
    (net (code "75") (name "S8") (class "Default")
      (node (ref "JR1") (pin "5") (pinfunction "5_5") (pintype "passive"))
      (node (ref "LB1") (pin "A8") (pinfunction "A_A8") (pintype "passive"))
      (node (ref "SWL1") (pin "9") (pinfunction "9_9") (pintype "passive"))
      (node (ref "SWR1") (pin "16") (pinfunction "16_16") (pintype "passive"))
    )
    (net (code "76") (name "S9") (class "Default")
      (node (ref "JL2") (pin "1") (pinfunction "1_1") (pintype "passive"))
      (node (ref "LB2") (pin "A1") (pinfunction "A_A1") (pintype "passive"))
      (node (ref "SWL2") (pin "16") (pinfunction "16_16") (pintype "passive"))
      (node (ref "SWR2") (pin "9") (pinfunction "9_9") (pintype "passive"))
    )
    (net (code "77") (name "S10") (class "Default")
      (node (ref "JR2") (pin "1") (pinfunction "1_1") (pintype "passive"))
      (node (ref "LB2") (pin "A2") (pinfunction "A_A2") (pintype "passive"))
      (node (ref "SWL2") (pin "15") (pinfunction "15_15") (pintype "passive"))
      (node (ref "SWR2") (pin "10") (pinfunction "10_10") (pintype "passive"))
    )
    (net (code "78") (name "S11") (class "Default")
      (node (ref "JL2") (pin "2") (pinfunction "2_2") (pintype "passive"))
      (node (ref "LB2") (pin "A3") (pinfunction "A_A3") (pintype "passive"))
      (node (ref "SWL2") (pin "14") (pinfunction "14_14") (pintype "passive"))
      (node (ref "SWR2") (pin "11") (pinfunction "11_11") (pintype "passive"))
    )
    (net (code "79") (name "S12") (class "Default")
      (node (ref "JR2") (pin "2") (pinfunction "2_2") (pintype "passive"))
      (node (ref "LB2") (pin "A4") (pinfunction "A_A4") (pintype "passive"))
      (node (ref "SWL2") (pin "13") (pinfunction "13_13") (pintype "passive"))
      (node (ref "SWR2") (pin "12") (pinfunction "12_12") (pintype "passive"))
    )
    (net (code "80") (name "S13") (class "Default")
      (node (ref "JL2") (pin "4") (pinfunction "4_4") (pintype "passive"))
      (node (ref "LB2") (pin "A5") (pinfunction "A_A5") (pintype "passive"))
      (node (ref "SWL2") (pin "12") (pinfunction "12_12") (pintype "passive"))
      (node (ref "SWR2") (pin "13") (pinfunction "13_13") (pintype "passive"))
    )
    (net (code "81") (name "S14") (class "Default")
      (node (ref "JR2") (pin "4") (pinfunction "4_4") (pintype "passive"))
      (node (ref "LB2") (pin "A6") (pinfunction "A_A6") (pintype "passive"))
      (node (ref "SWL2") (pin "11") (pinfunction "11_11") (pintype "passive"))
      (node (ref "SWR2") (pin "14") (pinfunction "14_14") (pintype "passive"))
    )
    (net (code "82") (name "S15") (class "Default")
      (node (ref "JL2") (pin "5") (pinfunction "5_5") (pintype "passive"))
      (node (ref "LB2") (pin "A7") (pinfunction "A_A7") (pintype "passive"))
      (node (ref "SWL2") (pin "10") (pinfunction "10_10") (pintype "passive"))
      (node (ref "SWR2") (pin "15") (pinfunction "15_15") (pintype "passive"))
    )
    (net (code "83") (name "S16") (class "Default")
      (node (ref "JR2") (pin "5") (pinfunction "5_5") (pintype "passive"))
      (node (ref "SWL2") (pin "9") (pinfunction "9_9") (pintype "passive"))
      (node (ref "SWR2") (pin "16") (pinfunction "16_16") (pintype "passive"))
    )
    (net (code "84") (name "S17") (class "Default")
      (node (ref "JL3") (pin "1") (pinfunction "1_1") (pintype "passive"))
      (node (ref "LB3") (pin "A1") (pinfunction "A_A1") (pintype "passive"))
      (node (ref "SWL3") (pin "16") (pinfunction "16_16") (pintype "passive"))
      (node (ref "SWR3") (pin "9") (pinfunction "9_9") (pintype "passive"))
    )
    (net (code "85") (name "S18") (class "Default")
      (node (ref "JR3") (pin "1") (pinfunction "1_1") (pintype "passive"))
      (node (ref "LB3") (pin "A2") (pinfunction "A_A2") (pintype "passive"))
      (node (ref "SWL3") (pin "15") (pinfunction "15_15") (pintype "passive"))
      (node (ref "SWR3") (pin "10") (pinfunction "10_10") (pintype "passive"))
    )
    (net (code "86") (name "S19") (class "Default")
      (node (ref "JL3") (pin "2") (pinfunction "2_2") (pintype "passive"))
      (node (ref "LB3") (pin "A3") (pinfunction "A_A3") (pintype "passive"))
      (node (ref "SWL3") (pin "14") (pinfunction "14_14") (pintype "passive"))
      (node (ref "SWR3") (pin "11") (pinfunction "11_11") (pintype "passive"))
    )
    (net (code "87") (name "S20") (class "Default")
      (node (ref "JR3") (pin "2") (pinfunction "2_2") (pintype "passive"))
      (node (ref "LB3") (pin "A4") (pinfunction "A_A4") (pintype "passive"))
      (node (ref "SWL3") (pin "13") (pinfunction "13_13") (pintype "passive"))
      (node (ref "SWR3") (pin "12") (pinfunction "12_12") (pintype "passive"))
    )
    (net (code "88") (name "S21") (class "Default")
      (node (ref "JL3") (pin "4") (pinfunction "4_4") (pintype "passive"))
      (node (ref "LB3") (pin "A5") (pinfunction "A_A5") (pintype "passive"))
      (node (ref "SWL3") (pin "12") (pinfunction "12_12") (pintype "passive"))
      (node (ref "SWR3") (pin "13") (pinfunction "13_13") (pintype "passive"))
    )
    (net (code "89") (name "S22") (class "Default")
      (node (ref "JR3") (pin "4") (pinfunction "4_4") (pintype "passive"))
      (node (ref "LB3") (pin "A6") (pinfunction "A_A6") (pintype "passive"))
      (node (ref "SWL3") (pin "11") (pinfunction "11_11") (pintype "passive"))
      (node (ref "SWR3") (pin "14") (pinfunction "14_14") (pintype "passive"))
    )
    (net (code "90") (name "S23") (class "Default")
      (node (ref "JL3") (pin "5") (pinfunction "5_5") (pintype "passive"))
      (node (ref "LB3") (pin "A7") (pinfunction "A_A7") (pintype "passive"))
      (node (ref "SWL3") (pin "10") (pinfunction "10_10") (pintype "passive"))
      (node (ref "SWR3") (pin "15") (pinfunction "15_15") (pintype "passive"))
    )
    (net (code "91") (name "S24") (class "Default")
      (node (ref "JR3") (pin "5") (pinfunction "5_5") (pintype "passive"))
      (node (ref "LB3") (pin "A8") (pinfunction "A_A8") (pintype "passive"))
      (node (ref "SWL3") (pin "9") (pinfunction "9_9") (pintype "passive"))
      (node (ref "SWR3") (pin "16") (pinfunction "16_16") (pintype "passive"))
    )
    (net (code "92") (name "S25") (class "Default")
      (node (ref "JL4") (pin "1") (pinfunction "1_1") (pintype "passive"))
      (node (ref "LB4") (pin "A1") (pinfunction "A_A1") (pintype "passive"))
      (node (ref "SWL4") (pin "16") (pinfunction "16_16") (pintype "passive"))
      (node (ref "SWR4") (pin "9") (pinfunction "9_9") (pintype "passive"))
    )
    (net (code "93") (name "S26") (class "Default")
      (node (ref "JR4") (pin "1") (pinfunction "1_1") (pintype "passive"))
      (node (ref "LB4") (pin "A2") (pinfunction "A_A2") (pintype "passive"))
      (node (ref "SWL4") (pin "15") (pinfunction "15_15") (pintype "passive"))
      (node (ref "SWR4") (pin "10") (pinfunction "10_10") (pintype "passive"))
    )
    (net (code "94") (name "S27") (class "Default")
      (node (ref "JL4") (pin "2") (pinfunction "2_2") (pintype "passive"))
      (node (ref "LB4") (pin "A3") (pinfunction "A_A3") (pintype "passive"))
      (node (ref "SWL4") (pin "14") (pinfunction "14_14") (pintype "passive"))
      (node (ref "SWR4") (pin "11") (pinfunction "11_11") (pintype "passive"))
    )
    (net (code "95") (name "S28") (class "Default")
      (node (ref "JR4") (pin "2") (pinfunction "2_2") (pintype "passive"))
      (node (ref "LB4") (pin "A4") (pinfunction "A_A4") (pintype "passive"))
      (node (ref "SWL4") (pin "13") (pinfunction "13_13") (pintype "passive"))
      (node (ref "SWR4") (pin "12") (pinfunction "12_12") (pintype "passive"))
    )
    (net (code "96") (name "S29") (class "Default")
      (node (ref "JL4") (pin "4") (pinfunction "4_4") (pintype "passive"))
      (node (ref "LB4") (pin "A5") (pinfunction "A_A5") (pintype "passive"))
      (node (ref "SWL4") (pin "12") (pinfunction "12_12") (pintype "passive"))
      (node (ref "SWR4") (pin "13") (pinfunction "13_13") (pintype "passive"))
    )
    (net (code "97") (name "S30") (class "Default")
      (node (ref "JR4") (pin "4") (pinfunction "4_4") (pintype "passive"))
      (node (ref "LB4") (pin "A6") (pinfunction "A_A6") (pintype "passive"))
      (node (ref "SWL4") (pin "11") (pinfunction "11_11") (pintype "passive"))
      (node (ref "SWR4") (pin "14") (pinfunction "14_14") (pintype "passive"))
    )
    (net (code "98") (name "S31") (class "Default")
      (node (ref "JL4") (pin "5") (pinfunction "5_5") (pintype "passive"))
      (node (ref "LB4") (pin "A7") (pinfunction "A_A7") (pintype "passive"))
      (node (ref "SWL4") (pin "10") (pinfunction "10_10") (pintype "passive"))
      (node (ref "SWR4") (pin "15") (pinfunction "15_15") (pintype "passive"))
    )
    (net (code "99") (name "S32") (class "Default")
      (node (ref "JR4") (pin "5") (pinfunction "5_5") (pintype "passive"))
      (node (ref "LB4") (pin "A8") (pinfunction "A_A8") (pintype "passive"))
      (node (ref "SWL4") (pin "9") (pinfunction "9_9") (pintype "passive"))
      (node (ref "SWR4") (pin "16") (pinfunction "16_16") (pintype "passive"))
    )
    (net (code "100") (name "unconnected-(HEADER_RULER-Pad1)") (class "Default")
      (node (ref "HEADER_RULER") (pin "1") (pinfunction "1_1") (pintype "passive"))
    )
    (net (code "101") (name "unconnected-(HEADER_RULER-Pad2)") (class "Default")
      (node (ref "HEADER_RULER") (pin "2") (pinfunction "2_2") (pintype "passive"))
    )
    (net (code "102") (name "unconnected-(HEADER_RULER-Pad3)") (class "Default")
      (node (ref "HEADER_RULER") (pin "3") (pinfunction "3_3") (pintype "passive"))
    )
    (net (code "103") (name "unconnected-(HEADER_RULER-Pad4)") (class "Default")
      (node (ref "HEADER_RULER") (pin "4") (pinfunction "4_4") (pintype "passive"))
    )
    (net (code "104") (name "unconnected-(HEADER_RULER-Pad5)") (class "Default")
      (node (ref "HEADER_RULER") (pin "5") (pinfunction "5_5") (pintype "passive"))
    )
    (net (code "105") (name "unconnected-(HEADER_RULER-Pad6)") (class "Default")
      (node (ref "HEADER_RULER") (pin "6") (pinfunction "6_6") (pintype "passive"))
    )
    (net (code "106") (name "unconnected-(HEADER_RULER-Pad7)") (class "Default")
      (node (ref "HEADER_RULER") (pin "7") (pinfunction "7_7") (pintype "passive"))
    )
    (net (code "107") (name "unconnected-(HEADER_RULER-Pad8)") (class "Default")
      (node (ref "HEADER_RULER") (pin "8") (pinfunction "8_8") (pintype "passive"))
    )
    (net (code "108") (name "unconnected-(HEADER_RULER-Pad9)") (class "Default")
      (node (ref "HEADER_RULER") (pin "9") (pinfunction "9_9") (pintype "passive"))
    )
    (net (code "109") (name "unconnected-(HEADER_RULER-Pad10)") (class "Default")
      (node (ref "HEADER_RULER") (pin "10") (pinfunction "10_10") (pintype "passive"))
    )
    (net (code "110") (name "unconnected-(HEADER_RULER-Pad11)") (class "Default")
      (node (ref "HEADER_RULER") (pin "11") (pinfunction "11_11") (pintype "passive"))
    )
    (net (code "111") (name "unconnected-(HEADER_RULER-Pad12)") (class "Default")
      (node (ref "HEADER_RULER") (pin "12") (pinfunction "12_12") (pintype "passive"))
    )
    (net (code "112") (name "unconnected-(HEADER_RULER-Pad13)") (class "Default")
      (node (ref "HEADER_RULER") (pin "13") (pinfunction "13_13") (pintype "passive"))
    )
    (net (code "113") (name "unconnected-(HEADER_RULER-Pad14)") (class "Default")
      (node (ref "HEADER_RULER") (pin "14") (pinfunction "14_14") (pintype "passive"))
    )
    (net (code "114") (name "unconnected-(HEADER_RULER-Pad15)") (class "Default")
      (node (ref "HEADER_RULER") (pin "15") (pinfunction "15_15") (pintype "passive"))
    )
    (net (code "115") (name "unconnected-(HEADER_RULER-Pad16)") (class "Default")
      (node (ref "HEADER_RULER") (pin "16") (pinfunction "16_16") (pintype "passive"))
    )
    (net (code "116") (name "unconnected-(HEADER_RULER-Pad17)") (class "Default")
      (node (ref "HEADER_RULER") (pin "17") (pinfunction "17_17") (pintype "passive"))
    )
    (net (code "117") (name "unconnected-(HEADER_RULER-Pad18)") (class "Default")
      (node (ref "HEADER_RULER") (pin "18") (pinfunction "18_18") (pintype "passive"))
    )
    (net (code "118") (name "unconnected-(HEADER_RULER-Pad19)") (class "Default")
      (node (ref "HEADER_RULER") (pin "19") (pinfunction "19_19") (pintype "passive"))
    )
    (net (code "119") (name "unconnected-(HEADER_RULER-Pad20)") (class "Default")
      (node (ref "HEADER_RULER") (pin "20") (pinfunction "20_20") (pintype "passive"))
    )
    (net (code "120") (name "unconnected-(HEADER_RULER-Pad21)") (class "Default")
      (node (ref "HEADER_RULER") (pin "21") (pinfunction "21_21") (pintype "passive"))
    )
    (net (code "121") (name "unconnected-(HEADER_RULER-Pad22)") (class "Default")
      (node (ref "HEADER_RULER") (pin "22") (pinfunction "22_22") (pintype "passive"))
    )
    (net (code "122") (name "unconnected-(HEADER_RULER-Pad23)") (class "Default")
      (node (ref "HEADER_RULER") (pin "23") (pinfunction "23_23") (pintype "passive"))
    )
    (net (code "123") (name "unconnected-(HEADER_RULER-Pad24)") (class "Default")
      (node (ref "HEADER_RULER") (pin "24") (pinfunction "24_24") (pintype "passive"))
    )
    (net (code "124") (name "unconnected-(HEADER_RULER-Pad25)") (class "Default")
      (node (ref "HEADER_RULER") (pin "25") (pinfunction "25_25") (pintype "passive"))
    )
    (net (code "125") (name "unconnected-(HEADER_RULER-Pad26)") (class "Default")
      (node (ref "HEADER_RULER") (pin "26") (pinfunction "26_26") (pintype "passive"))
    )
    (net (code "126") (name "unconnected-(HEADER_RULER-Pad27)") (class "Default")
      (node (ref "HEADER_RULER") (pin "27") (pinfunction "27_27") (pintype "passive"))
    )
    (net (code "127") (name "unconnected-(HEADER_RULER-Pad28)") (class "Default")
      (node (ref "HEADER_RULER") (pin "28") (pinfunction "28_28") (pintype "passive"))
    )
    (net (code "128") (name "unconnected-(HEADER_RULER-Pad29)") (class "Default")
      (node (ref "HEADER_RULER") (pin "29") (pinfunction "29_29") (pintype "passive"))
    )
    (net (code "129") (name "unconnected-(HEADER_RULER-Pad30)") (class "Default")
      (node (ref "HEADER_RULER") (pin "30") (pinfunction "30_30") (pintype "passive"))
    )
    (net (code "130") (name "unconnected-(HEADER_RULER-Pad31)") (class "Default")
      (node (ref "HEADER_RULER") (pin "31") (pinfunction "31_31") (pintype "passive"))
    )
    (net (code "131") (name "unconnected-(HEADER_RULER-Pad32)") (class "Default")
      (node (ref "HEADER_RULER") (pin "32") (pinfunction "32_32") (pintype "passive"))
    )
    (net (code "132") (name "unconnected-(HEADER_RULER-Pad33)") (class "Default")
      (node (ref "HEADER_RULER") (pin "33") (pinfunction "33_33") (pintype "passive"))
    )
    (net (code "133") (name "unconnected-(HEADER_RULER-Pad34)") (class "Default")
      (node (ref "HEADER_RULER") (pin "34") (pinfunction "34_34") (pintype "passive"))
    )
    (net (code "134") (name "unconnected-(HEADER_RULER-Pad35)") (class "Default")
      (node (ref "HEADER_RULER") (pin "35") (pinfunction "35_35") (pintype "passive"))
    )
    (net (code "135") (name "unconnected-(HEADER_RULER-Pad36)") (class "Default")
      (node (ref "HEADER_RULER") (pin "36") (pinfunction "36_36") (pintype "passive"))
    )
    (net (code "136") (name "unconnected-(HEADER_RULER-Pad37)") (class "Default")
      (node (ref "HEADER_RULER") (pin "37") (pinfunction "37_37") (pintype "passive"))
    )
    (net (code "137") (name "unconnected-(HEADER_RULER-Pad38)") (class "Default")
      (node (ref "HEADER_RULER") (pin "38") (pinfunction "38_38") (pintype "passive"))
    )
    (net (code "138") (name "unconnected-(HEADER_RULER-Pad39)") (class "Default")
      (node (ref "HEADER_RULER") (pin "39") (pinfunction "39_39") (pintype "passive"))
    )
    (net (code "139") (name "unconnected-(HEADER_RULER-Pad40)") (class "Default")
      (node (ref "HEADER_RULER") (pin "40") (pinfunction "40_40") (pintype "passive"))
    )
    (net (code "140") (name "unconnected-(JL1-Pad3)") (class "Default")
      (node (ref "JL1") (pin "3") (pinfunction "3_3") (pintype "passive"))
    )
    (net (code "141") (name "unconnected-(JL2-Pad3)") (class "Default")
      (node (ref "JL2") (pin "3") (pinfunction "3_3") (pintype "passive"))
    )
    (net (code "142") (name "unconnected-(JL3-Pad3)") (class "Default")
      (node (ref "JL3") (pin "3") (pinfunction "3_3") (pintype "passive"))
    )
    (net (code "143") (name "unconnected-(JL4-Pad3)") (class "Default")
      (node (ref "JL4") (pin "3") (pinfunction "3_3") (pintype "passive"))
    )
    (net (code "144") (name "unconnected-(JR1-Pad3)") (class "Default")
      (node (ref "JR1") (pin "3") (pinfunction "3_3") (pintype "passive"))
    )
    (net (code "145") (name "unconnected-(JR2-Pad3)") (class "Default")
      (node (ref "JR2") (pin "3") (pinfunction "3_3") (pintype "passive"))
    )
    (net (code "146") (name "unconnected-(JR3-Pad3)") (class "Default")
      (node (ref "JR3") (pin "3") (pinfunction "3_3") (pintype "passive"))
    )
    (net (code "147") (name "unconnected-(JR4-Pad3)") (class "Default")
      (node (ref "JR4") (pin "3") (pinfunction "3_3") (pintype "passive"))
    )
    (net (code "148") (name "unconnected-(LB2H-A-PadA8)") (class "Default")
      (node (ref "LB2") (pin "A8") (pinfunction "A_A8") (pintype "passive"))
    )
  )
)
